# sla2216-comp.net
KiCad netlist of a schematic drawn in Altium Designer
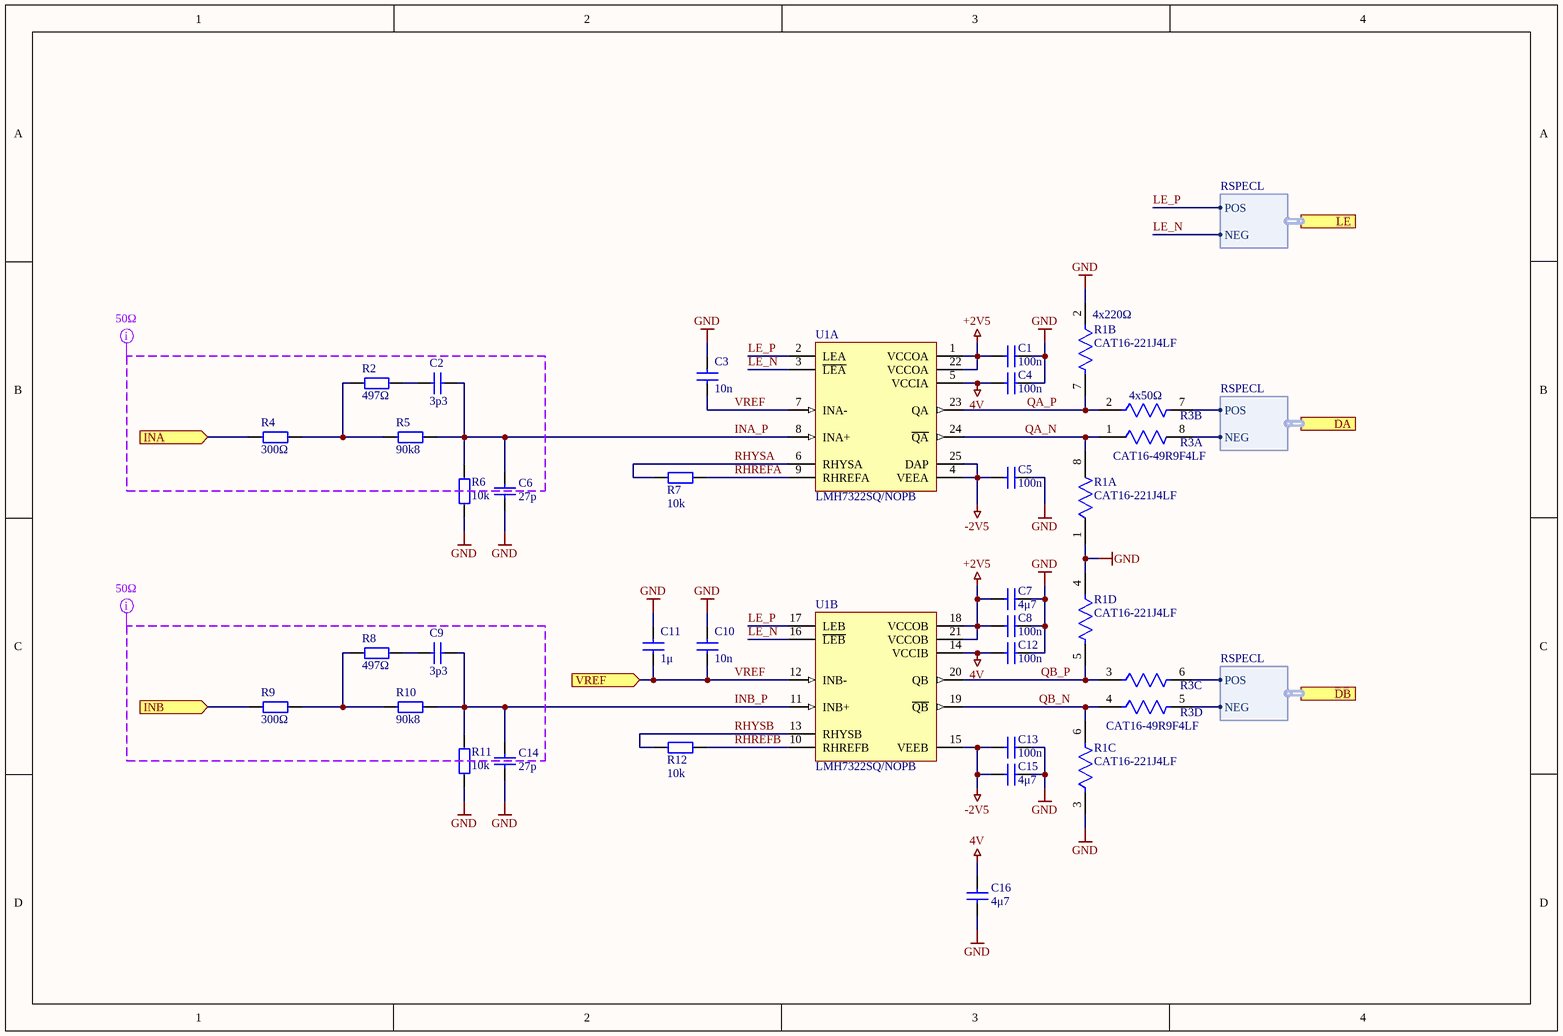
[diagram p0: sla2216-comp.SchDoc]

(export (version "E")
  (design (tool "Eeschema 10.0.6"))
  (components
    (comp (ref "C1")
      (value "~")
      (footprint "CAP 0402/1005")
      (description "Ceramic Capacitor")
      (fields (field (name "TOLERANCE") "10%") (field (name "CAPACITANCE") "100n"))
      (libsource (lib "altium_lib") (part "Capacitor"))
    )
    (comp (ref "C2")
      (value "~")
      (footprint "CAP 0402/1005")
      (description "Ceramic Capacitor")
      (fields (field (name "TOLERANCE") "10%") (field (name "CAPACITANCE") "3p3"))
      (libsource (lib "altium_lib") (part "Capacitor"))
    )
    (comp (ref "C3")
      (value "~")
      (footprint "CAP 0402/1005")
      (description "Ceramic Capacitor")
      (fields (field (name "TOLERANCE") "10%") (field (name "CAPACITANCE") "10n"))
      (libsource (lib "altium_lib") (part "Capacitor"))
    )
    (comp (ref "C4")
      (value "~")
      (footprint "CAP 0402/1005")
      (description "Ceramic Capacitor")
      (fields (field (name "TOLERANCE") "10%") (field (name "CAPACITANCE") "100n"))
      (libsource (lib "altium_lib") (part "Capacitor"))
    )
    (comp (ref "C5")
      (value "~")
      (footprint "CAP 0402/1005")
      (description "Ceramic Capacitor")
      (fields (field (name "TOLERANCE") "10%") (field (name "CAPACITANCE") "100n"))
      (libsource (lib "altium_lib") (part "Capacitor"))
    )
    (comp (ref "C6")
      (value "~")
      (footprint "CAP 0402/1005")
      (description "Ceramic Capacitor")
      (fields (field (name "TOLERANCE") "10%") (field (name "CAPACITANCE") "27p"))
      (libsource (lib "altium_lib") (part "Capacitor"))
    )
    (comp (ref "C7")
      (value "~")
      (footprint "CAP 0603/1608")
      (description "Ceramic Capacitor")
      (fields (field (name "TOLERANCE") "10%") (field (name "CAPACITANCE") "4μ7"))
      (libsource (lib "altium_lib") (part "Capacitor"))
    )
    (comp (ref "C8")
      (value "~")
      (footprint "CAP 0402/1005")
      (description "Ceramic Capacitor")
      (fields (field (name "TOLERANCE") "10%") (field (name "CAPACITANCE") "100n"))
      (libsource (lib "altium_lib") (part "Capacitor"))
    )
    (comp (ref "C9")
      (value "~")
      (footprint "CAP 0402/1005")
      (description "Ceramic Capacitor")
      (fields (field (name "TOLERANCE") "10%") (field (name "CAPACITANCE") "3p3"))
      (libsource (lib "altium_lib") (part "Capacitor"))
    )
    (comp (ref "C10")
      (value "~")
      (footprint "CAP 0402/1005")
      (description "Ceramic Capacitor")
      (fields (field (name "TOLERANCE") "10%") (field (name "CAPACITANCE") "10n"))
      (libsource (lib "altium_lib") (part "Capacitor"))
    )
    (comp (ref "C11")
      (value "~")
      (footprint "CAP 0603/1608")
      (description "Ceramic Capacitor")
      (fields (field (name "TOLERANCE") "10%") (field (name "CAPACITANCE") "1μ"))
      (libsource (lib "altium_lib") (part "Capacitor"))
    )
    (comp (ref "C12")
      (value "~")
      (footprint "CAP 0402/1005")
      (description "Ceramic Capacitor")
      (fields (field (name "TOLERANCE") "10%") (field (name "CAPACITANCE") "100n"))
      (libsource (lib "altium_lib") (part "Capacitor"))
    )
    (comp (ref "C13")
      (value "~")
      (footprint "CAP 0402/1005")
      (description "Ceramic Capacitor")
      (fields (field (name "TOLERANCE") "10%") (field (name "CAPACITANCE") "100n"))
      (libsource (lib "altium_lib") (part "Capacitor"))
    )
    (comp (ref "C14")
      (value "~")
      (footprint "CAP 0402/1005")
      (description "Ceramic Capacitor")
      (fields (field (name "TOLERANCE") "10%") (field (name "CAPACITANCE") "27p"))
      (libsource (lib "altium_lib") (part "Capacitor"))
    )
    (comp (ref "C15")
      (value "~")
      (footprint "CAP 0603/1608")
      (description "Ceramic Capacitor")
      (fields (field (name "TOLERANCE") "10%") (field (name "CAPACITANCE") "4μ7"))
      (libsource (lib "altium_lib") (part "Capacitor"))
    )
    (comp (ref "C16")
      (value "~")
      (footprint "CAP 0603/1608")
      (description "Ceramic Capacitor")
      (fields (field (name "TOLERANCE") "10%") (field (name "CAPACITANCE") "4μ7"))
      (libsource (lib "altium_lib") (part "Capacitor"))
    )
    (comp (ref "R1")
      (value "CAT16-221J4LF")
      (footprint "FP-CAT16-F4-MFG")
      (description "RES ARRAY 4 RES 220 OHM 1206")
      (fields (field (name "TOLERANCE") "1%"))
      (libsource (lib "Altium Content Vault") (part "7d582628e90f98138909bd7e7c1f9a4"))
    )
    (comp (ref "R2")
      (value "~")
      (footprint "RES 0402/1005")
      (description "Resistor")
      (fields (field (name "TOLERANCE") "5%") (field (name "RESISTANCE") "497Ω"))
      (libsource (lib "altium_lib") (part "Resistor"))
    )
    (comp (ref "R3")
      (value "CAT16-49R9F4LF")
      (footprint "FP-CAT16-F4-MFG")
      (description "RES ARRAY 4 RES 49.9 OHM 1206")
      (fields (field (name "TOLERANCE") "1%"))
      (libsource (lib "Altium Content Vault") (part "7d582628e90f98138909bd7e7c1f9a4"))
    )
    (comp (ref "R4")
      (value "~")
      (footprint "RES 0805/2012")
      (description "Resistor")
      (fields (field (name "TOLERANCE") "5%") (field (name "RESISTANCE") "300Ω"))
      (libsource (lib "altium_lib") (part "Resistor"))
    )
    (comp (ref "R5")
      (value "~")
      (footprint "RES 0402/1005")
      (description "Resistor")
      (fields (field (name "TOLERANCE") "5%") (field (name "RESISTANCE") "90k8"))
      (libsource (lib "altium_lib") (part "Resistor"))
    )
    (comp (ref "R6")
      (value "~")
      (footprint "RES 0402/1005")
      (description "Resistor")
      (fields (field (name "TOLERANCE") "5%") (field (name "RESISTANCE") "10k"))
      (libsource (lib "altium_lib") (part "Resistor"))
    )
    (comp (ref "R7")
      (value "~")
      (footprint "RES 0402/1005")
      (description "Resistor")
      (fields (field (name "TOLERANCE") "5%") (field (name "RESISTANCE") "10k"))
      (libsource (lib "altium_lib") (part "Resistor"))
    )
    (comp (ref "R8")
      (value "~")
      (footprint "RES 0402/1005")
      (description "Resistor")
      (fields (field (name "TOLERANCE") "5%") (field (name "RESISTANCE") "497Ω"))
      (libsource (lib "altium_lib") (part "Resistor"))
    )
    (comp (ref "R9")
      (value "~")
      (footprint "RES 0805/2012")
      (description "Resistor")
      (fields (field (name "TOLERANCE") "5%") (field (name "RESISTANCE") "300Ω"))
      (libsource (lib "altium_lib") (part "Resistor"))
    )
    (comp (ref "R10")
      (value "~")
      (footprint "RES 0402/1005")
      (description "Resistor")
      (fields (field (name "TOLERANCE") "5%") (field (name "RESISTANCE") "90k8"))
      (libsource (lib "altium_lib") (part "Resistor"))
    )
    (comp (ref "R11")
      (value "~")
      (footprint "RES 0402/1005")
      (description "Resistor")
      (fields (field (name "TOLERANCE") "5%") (field (name "RESISTANCE") "10k"))
      (libsource (lib "altium_lib") (part "Resistor"))
    )
    (comp (ref "R12")
      (value "~")
      (footprint "RES 0402/1005")
      (description "Resistor")
      (fields (field (name "TOLERANCE") "5%") (field (name "RESISTANCE") "10k"))
      (libsource (lib "altium_lib") (part "Resistor"))
    )
    (comp (ref "U1")
      (value "LMH7322SQ/NOPB")
      (footprint "RTW0024A_V")
      (description "Dual 700 ps High Speed Comparator with RSPECL Outputs, 24-pin LLP, Pb-Free")
      (fields (field (name "MANUFACTURER") "Texas Instruments"))
      (libsource (lib "Altium Content Vault") (part "AN-COMP-LMH7322-25"))
    )
  )
  (nets
    (net (code "2") (name "+2V5") (class "Default")
      (node (ref "C1") (pin "2") (pinfunction "2_2") (pintype "passive"))
      (node (ref "C7") (pin "1") (pinfunction "1_1") (pintype "passive"))
      (node (ref "C8") (pin "2") (pinfunction "2_2") (pintype "passive"))
      (node (ref "U1") (pin "1") (pinfunction "VCCOA_1") (pintype "power_in"))
      (node (ref "U1") (pin "18") (pinfunction "VCCOB_18") (pintype "power_in"))
      (node (ref "U1") (pin "21") (pinfunction "VCCOB_21") (pintype "power_in"))
      (node (ref "U1") (pin "22") (pinfunction "VCCOA_22") (pintype "power_in"))
    )
    (net (code "3") (name "-2V5") (class "Default")
      (node (ref "C13") (pin "2") (pinfunction "2_2") (pintype "passive"))
      (node (ref "C15") (pin "1") (pinfunction "1_1") (pintype "passive"))
      (node (ref "C5") (pin "2") (pinfunction "2_2") (pintype "passive"))
      (node (ref "U1") (pin "15") (pinfunction "VEEB_15") (pintype "power_in"))
      (node (ref "U1") (pin "25") (pinfunction "DAP_25") (pintype "power_in"))
      (node (ref "U1") (pin "4") (pinfunction "VEEA_4") (pintype "power_in"))
    )
    (net (code "4") (name "/INA") (class "Default")
      (node (ref "R4") (pin "1") (pinfunction "1_1") (pintype "passive"))
    )
    (net (code "5") (name "/INA_P") (class "Default")
      (node (ref "C2") (pin "2") (pinfunction "2_2") (pintype "passive"))
      (node (ref "C6") (pin "1") (pinfunction "1_1") (pintype "passive"))
      (node (ref "R5") (pin "2") (pinfunction "2_2") (pintype "passive"))
      (node (ref "R6") (pin "1") (pinfunction "1_1") (pintype "passive"))
      (node (ref "U1") (pin "8") (pinfunction "INA+_8") (pintype "input"))
    )
    (net (code "6") (name "/INB") (class "Default")
      (node (ref "R9") (pin "1") (pinfunction "1_1") (pintype "passive"))
    )
    (net (code "7") (name "/INB_P") (class "Default")
      (node (ref "C14") (pin "1") (pinfunction "1_1") (pintype "passive"))
      (node (ref "C9") (pin "2") (pinfunction "2_2") (pintype "passive"))
      (node (ref "R10") (pin "2") (pinfunction "2_2") (pintype "passive"))
      (node (ref "R11") (pin "1") (pinfunction "1_1") (pintype "passive"))
      (node (ref "U1") (pin "11") (pinfunction "INB+_11") (pintype "input"))
    )
    (net (code "8") (name "/LE_N") (class "Default")
      (node (ref "U1") (pin "16") (pinfunction "~{LEB}_16") (pintype "passive"))
      (node (ref "U1") (pin "3") (pinfunction "~{LEA}_3") (pintype "passive"))
    )
    (net (code "9") (name "/LE_P") (class "Default")
      (node (ref "U1") (pin "17") (pinfunction "LEB_17") (pintype "passive"))
      (node (ref "U1") (pin "2") (pinfunction "LEA_2") (pintype "passive"))
    )
    (net (code "10") (name "/QA_N") (class "Default")
      (node (ref "R1") (pin "8") (pinfunction "8_8") (pintype "passive"))
      (node (ref "R3") (pin "1") (pinfunction "1_1") (pintype "passive"))
      (node (ref "U1") (pin "24") (pinfunction "~{QA}_24") (pintype "output"))
    )
    (net (code "11") (name "/QA_P") (class "Default")
      (node (ref "R1") (pin "7") (pinfunction "7_7") (pintype "passive"))
      (node (ref "R3") (pin "2") (pinfunction "2_2") (pintype "passive"))
      (node (ref "U1") (pin "23") (pinfunction "QA_23") (pintype "output"))
    )
    (net (code "12") (name "/QB_N") (class "Default")
      (node (ref "R1") (pin "6") (pinfunction "6_6") (pintype "passive"))
      (node (ref "R3") (pin "4") (pinfunction "4_4") (pintype "passive"))
      (node (ref "U1") (pin "19") (pinfunction "~{QB}_19") (pintype "output"))
    )
    (net (code "13") (name "/QB_P") (class "Default")
      (node (ref "R1") (pin "5") (pinfunction "5_5") (pintype "passive"))
      (node (ref "R3") (pin "3") (pinfunction "3_3") (pintype "passive"))
      (node (ref "U1") (pin "20") (pinfunction "QB_20") (pintype "output"))
    )
    (net (code "14") (name "/RHREFA") (class "Default")
      (node (ref "R7") (pin "1") (pinfunction "1_1") (pintype "passive"))
      (node (ref "U1") (pin "9") (pinfunction "RHREFA_9") (pintype "passive"))
    )
    (net (code "15") (name "/RHREFB") (class "Default")
      (node (ref "R12") (pin "1") (pinfunction "1_1") (pintype "passive"))
      (node (ref "U1") (pin "10") (pinfunction "RHREFB_10") (pintype "passive"))
    )
    (net (code "16") (name "/RHYSA") (class "Default")
      (node (ref "R7") (pin "2") (pinfunction "2_2") (pintype "passive"))
      (node (ref "U1") (pin "6") (pinfunction "RHYSA_6") (pintype "passive"))
    )
    (net (code "17") (name "/RHYSB") (class "Default")
      (node (ref "R12") (pin "2") (pinfunction "2_2") (pintype "passive"))
      (node (ref "U1") (pin "13") (pinfunction "RHYSB_13") (pintype "passive"))
    )
    (net (code "18") (name "/VREF") (class "Default")
      (node (ref "C10") (pin "2") (pinfunction "2_2") (pintype "passive"))
      (node (ref "C11") (pin "1") (pinfunction "1_1") (pintype "passive"))
      (node (ref "C3") (pin "2") (pinfunction "2_2") (pintype "passive"))
      (node (ref "U1") (pin "12") (pinfunction "INB-_12") (pintype "input"))
      (node (ref "U1") (pin "7") (pinfunction "INA-_7") (pintype "input"))
    )
    (net (code "20") (name "4V") (class "Default")
      (node (ref "C12") (pin "2") (pinfunction "2_2") (pintype "passive"))
      (node (ref "C16") (pin "2") (pinfunction "2_2") (pintype "passive"))
      (node (ref "C4") (pin "2") (pinfunction "2_2") (pintype "passive"))
      (node (ref "U1") (pin "14") (pinfunction "VCCIB_14") (pintype "power_in"))
      (node (ref "U1") (pin "5") (pinfunction "VCCIA_5") (pintype "power_in"))
    )
    (net (code "21") (name "GND") (class "Default")
      (node (ref "C1") (pin "1") (pinfunction "1_1") (pintype "passive"))
      (node (ref "C10") (pin "1") (pinfunction "1_1") (pintype "passive"))
      (node (ref "C11") (pin "2") (pinfunction "2_2") (pintype "passive"))
      (node (ref "C12") (pin "1") (pinfunction "1_1") (pintype "passive"))
      (node (ref "C13") (pin "1") (pinfunction "1_1") (pintype "passive"))
      (node (ref "C14") (pin "2") (pinfunction "2_2") (pintype "passive"))
      (node (ref "C15") (pin "2") (pinfunction "2_2") (pintype "passive"))
      (node (ref "C16") (pin "1") (pinfunction "1_1") (pintype "passive"))
      (node (ref "C3") (pin "1") (pinfunction "1_1") (pintype "passive"))
      (node (ref "C4") (pin "1") (pinfunction "1_1") (pintype "passive"))
      (node (ref "C5") (pin "1") (pinfunction "1_1") (pintype "passive"))
      (node (ref "C6") (pin "2") (pinfunction "2_2") (pintype "passive"))
      (node (ref "C7") (pin "2") (pinfunction "2_2") (pintype "passive"))
      (node (ref "C8") (pin "1") (pinfunction "1_1") (pintype "passive"))
      (node (ref "R1") (pin "1") (pinfunction "1_1") (pintype "passive"))
      (node (ref "R1") (pin "2") (pinfunction "2_2") (pintype "passive"))
      (node (ref "R1") (pin "3") (pinfunction "3_3") (pintype "passive"))
      (node (ref "R1") (pin "4") (pinfunction "4_4") (pintype "passive"))
      (node (ref "R11") (pin "2") (pinfunction "2_2") (pintype "passive"))
      (node (ref "R6") (pin "2") (pinfunction "2_2") (pintype "passive"))
    )
    (net (code "22") (name "Net-(C2-Pad1)") (class "Default")
      (node (ref "C2") (pin "1") (pinfunction "1_1") (pintype "passive"))
      (node (ref "R2") (pin "2") (pinfunction "2_2") (pintype "passive"))
    )
    (net (code "23") (name "Net-(C9-Pad1)") (class "Default")
      (node (ref "C9") (pin "1") (pinfunction "1_1") (pintype "passive"))
      (node (ref "R8") (pin "2") (pinfunction "2_2") (pintype "passive"))
    )
    (net (code "24") (name "Net-(R2-Pad1)") (class "Default")
      (node (ref "R2") (pin "1") (pinfunction "1_1") (pintype "passive"))
      (node (ref "R4") (pin "2") (pinfunction "2_2") (pintype "passive"))
      (node (ref "R5") (pin "1") (pinfunction "1_1") (pintype "passive"))
    )
    (net (code "25") (name "Net-(R10-Pad1)") (class "Default")
      (node (ref "R10") (pin "1") (pinfunction "1_1") (pintype "passive"))
      (node (ref "R8") (pin "1") (pinfunction "1_1") (pintype "passive"))
      (node (ref "R9") (pin "2") (pinfunction "2_2") (pintype "passive"))
    )
    (net (code "26") (name "unconnected-(R3-Pad5)") (class "Default")
      (node (ref "R3") (pin "5") (pinfunction "5_5") (pintype "passive"))
    )
    (net (code "27") (name "unconnected-(R3-Pad6)") (class "Default")
      (node (ref "R3") (pin "6") (pinfunction "6_6") (pintype "passive"))
    )
    (net (code "28") (name "unconnected-(R3-Pad7)") (class "Default")
      (node (ref "R3") (pin "7") (pinfunction "7_7") (pintype "passive"))
    )
    (net (code "29") (name "unconnected-(R3-Pad8)") (class "Default")
      (node (ref "R3") (pin "8") (pinfunction "8_8") (pintype "passive"))
    )
  )
)
